# shieldv1.net
KiCad netlist of a schematic drawn in EAGLE
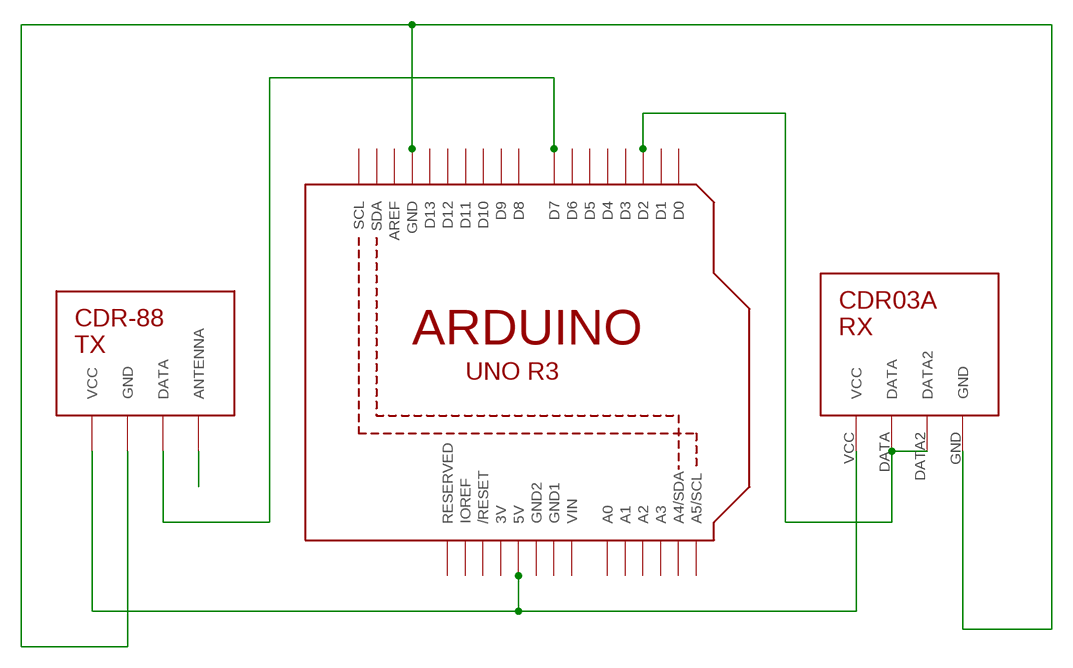
[diagram p0: schematic, sheet 1]

(export (version "E")
  (design (tool "Eeschema 10.0.6"))
  (components
    (comp (ref "U$1")
      (value "CDT-88")
      (footprint "eagle-import:CDT-88")
      (libsource (lib "eagle-import") (part "CDT-88"))
    )
    (comp (ref "U$2")
      (value "CDR03A")
      (footprint "eagle-import:CDR03A")
      (libsource (lib "eagle-import") (part "CDR03A"))
    )
    (comp (ref "U2")
      (value "ARDUINOR3-DIMENSION")
      (footprint "eagle-import:ARDUINOR3")
      (libsource (lib "eagle-import") (part "ARDUINOR3-DIMENSION"))
    )
  )
  (nets
    (net (code "1") (name "/3V") (class "Default")
      (node (ref "U2") (pin "3V") (pinfunction "3V_3V") (pintype "power_in"))
    )
    (net (code "2") (name "/GND1") (class "Default")
      (node (ref "U2") (pin "GND1") (pinfunction "GND1_GND1") (pintype "power_in"))
    )
    (net (code "3") (name "/GND2") (class "Default")
      (node (ref "U2") (pin "GND2") (pinfunction "GND2_GND2") (pintype "power_in"))
    )
    (net (code "4") (name "/VIN") (class "Default")
      (node (ref "U2") (pin "VIN") (pinfunction "VIN_VIN") (pintype "power_in"))
    )
    (net (code "5") (name "Net-(U$1-PadDATA)") (class "Default")
      (node (ref "U$1") (pin "DATA") (pinfunction "DATA_DATA") (pintype "bidirectional"))
      (node (ref "U2") (pin "D7") (pinfunction "D7_D7") (pintype "bidirectional"))
    )
    (net (code "6") (name "Net-(U$1-PadGND)") (class "Default")
      (node (ref "U$1") (pin "GND") (pinfunction "GND_GND") (pintype "bidirectional"))
      (node (ref "U$2") (pin "GND") (pinfunction "GND_GND") (pintype "bidirectional"))
      (node (ref "U2") (pin "GND") (pinfunction "GND_GND") (pintype "power_in"))
    )
    (net (code "7") (name "Net-(U$1-PadVCC)") (class "Default")
      (node (ref "U$1") (pin "VCC") (pinfunction "VCC_VCC") (pintype "bidirectional"))
      (node (ref "U$2") (pin "VCC") (pinfunction "VCC_VCC") (pintype "bidirectional"))
      (node (ref "U2") (pin "5V") (pinfunction "5V_5V") (pintype "power_in"))
    )
    (net (code "8") (name "Net-(U$2-PadDATA)") (class "Default")
      (node (ref "U$2") (pin "DATA") (pinfunction "DATA_DATA") (pintype "bidirectional"))
      (node (ref "U$2") (pin "DATA2") (pinfunction "DATA2_DATA2") (pintype "bidirectional"))
      (node (ref "U2") (pin "D2") (pinfunction "D2_D2") (pintype "bidirectional"))
    )
    (net (code "9") (name "unconnected-(U$1-PadANTENNA)") (class "Default")
      (node (ref "U$1") (pin "ANTENNA") (pinfunction "ANTENNA_ANTENNA") (pintype "bidirectional"))
    )
    (net (code "10") (name "unconnected-(U2-A4{slash}SDA-PadA4)") (class "Default")
      (node (ref "U2") (pin "A4") (pinfunction "A4/SDA_A4") (pintype "bidirectional"))
    )
    (net (code "11") (name "unconnected-(U2-A5{slash}SCL-PadA5)") (class "Default")
      (node (ref "U2") (pin "A5") (pinfunction "A5/SCL_A5") (pintype "bidirectional"))
    )
    (net (code "12") (name "unconnected-(U2-PadA0)") (class "Default")
      (node (ref "U2") (pin "A0") (pinfunction "A0_A0") (pintype "bidirectional"))
    )
    (net (code "13") (name "unconnected-(U2-PadA1)") (class "Default")
      (node (ref "U2") (pin "A1") (pinfunction "A1_A1") (pintype "bidirectional"))
    )
    (net (code "14") (name "unconnected-(U2-PadA2)") (class "Default")
      (node (ref "U2") (pin "A2") (pinfunction "A2_A2") (pintype "bidirectional"))
    )
    (net (code "15") (name "unconnected-(U2-PadA3)") (class "Default")
      (node (ref "U2") (pin "A3") (pinfunction "A3_A3") (pintype "bidirectional"))
    )
    (net (code "16") (name "unconnected-(U2-PadAREF)") (class "Default")
      (node (ref "U2") (pin "AREF") (pinfunction "AREF_AREF") (pintype "bidirectional"))
    )
    (net (code "17") (name "unconnected-(U2-PadD0)") (class "Default")
      (node (ref "U2") (pin "D0") (pinfunction "D0_D0") (pintype "bidirectional"))
    )
    (net (code "18") (name "unconnected-(U2-PadD1)") (class "Default")
      (node (ref "U2") (pin "D1") (pinfunction "D1_D1") (pintype "bidirectional"))
    )
    (net (code "19") (name "unconnected-(U2-PadD3)") (class "Default")
      (node (ref "U2") (pin "D3") (pinfunction "D3_D3") (pintype "bidirectional"))
    )
    (net (code "20") (name "unconnected-(U2-PadD4)") (class "Default")
      (node (ref "U2") (pin "D4") (pinfunction "D4_D4") (pintype "bidirectional"))
    )
    (net (code "21") (name "unconnected-(U2-PadD5)") (class "Default")
      (node (ref "U2") (pin "D5") (pinfunction "D5_D5") (pintype "bidirectional"))
    )
    (net (code "22") (name "unconnected-(U2-PadD6)") (class "Default")
      (node (ref "U2") (pin "D6") (pinfunction "D6_D6") (pintype "bidirectional"))
    )
    (net (code "23") (name "unconnected-(U2-PadD8)") (class "Default")
      (node (ref "U2") (pin "D8") (pinfunction "D8_D8") (pintype "bidirectional"))
    )
    (net (code "24") (name "unconnected-(U2-PadD9)") (class "Default")
      (node (ref "U2") (pin "D9") (pinfunction "D9_D9") (pintype "bidirectional"))
    )
    (net (code "25") (name "unconnected-(U2-PadD10)") (class "Default")
      (node (ref "U2") (pin "D10") (pinfunction "D10_D10") (pintype "bidirectional"))
    )
    (net (code "26") (name "unconnected-(U2-PadD11)") (class "Default")
      (node (ref "U2") (pin "D11") (pinfunction "D11_D11") (pintype "bidirectional"))
    )
    (net (code "27") (name "unconnected-(U2-PadD12)") (class "Default")
      (node (ref "U2") (pin "D12") (pinfunction "D12_D12") (pintype "bidirectional"))
    )
    (net (code "28") (name "unconnected-(U2-PadD13)") (class "Default")
      (node (ref "U2") (pin "D13") (pinfunction "D13_D13") (pintype "bidirectional"))
    )
    (net (code "29") (name "unconnected-(U2-PadIOREF)") (class "Default")
      (node (ref "U2") (pin "IOREF") (pinfunction "IOREF_IOREF") (pintype "output"))
    )
    (net (code "30") (name "unconnected-(U2-PadRESERVED)") (class "Default")
      (node (ref "U2") (pin "RESERVED") (pinfunction "RESERVED_RESERVED") (pintype "no_connect"))
    )
    (net (code "31") (name "unconnected-(U2-PadSCL)") (class "Default")
      (node (ref "U2") (pin "SCL") (pinfunction "SCL_SCL") (pintype "bidirectional"))
    )
    (net (code "32") (name "unconnected-(U2-PadSDA)") (class "Default")
      (node (ref "U2") (pin "SDA") (pinfunction "SDA_SDA") (pintype "bidirectional"))
    )
    (net (code "33") (name "unconnected-(U2-{slash}RESET-PadRESET)") (class "Default")
      (node (ref "U2") (pin "RESET") (pinfunction "/RESET_RESET") (pintype "bidirectional"))
    )
  )
)
